# shield.net
KiCad netlist of a schematic drawn in EAGLE
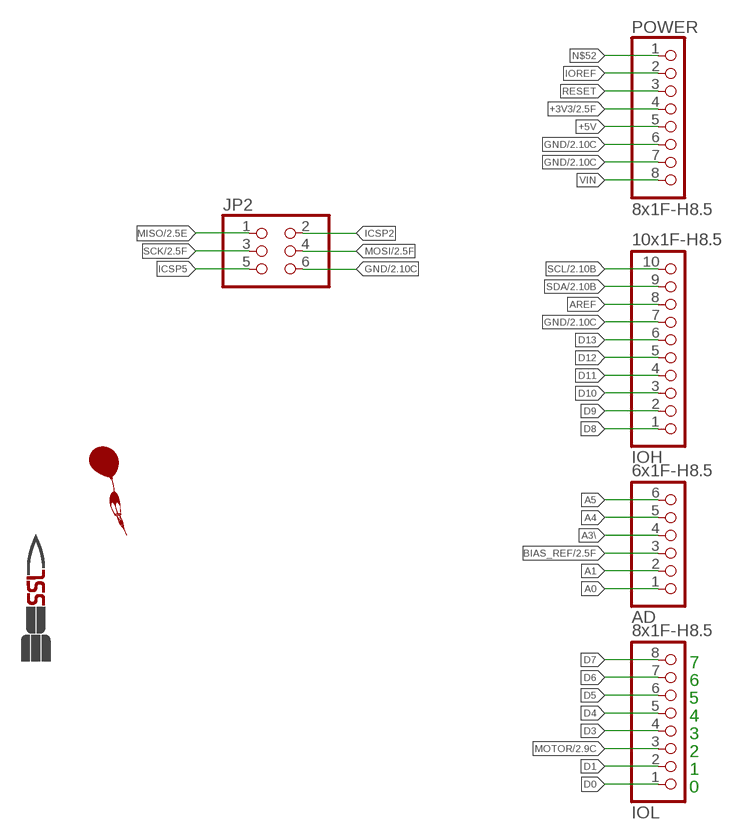
[diagram p0: schematic, sheet 1]
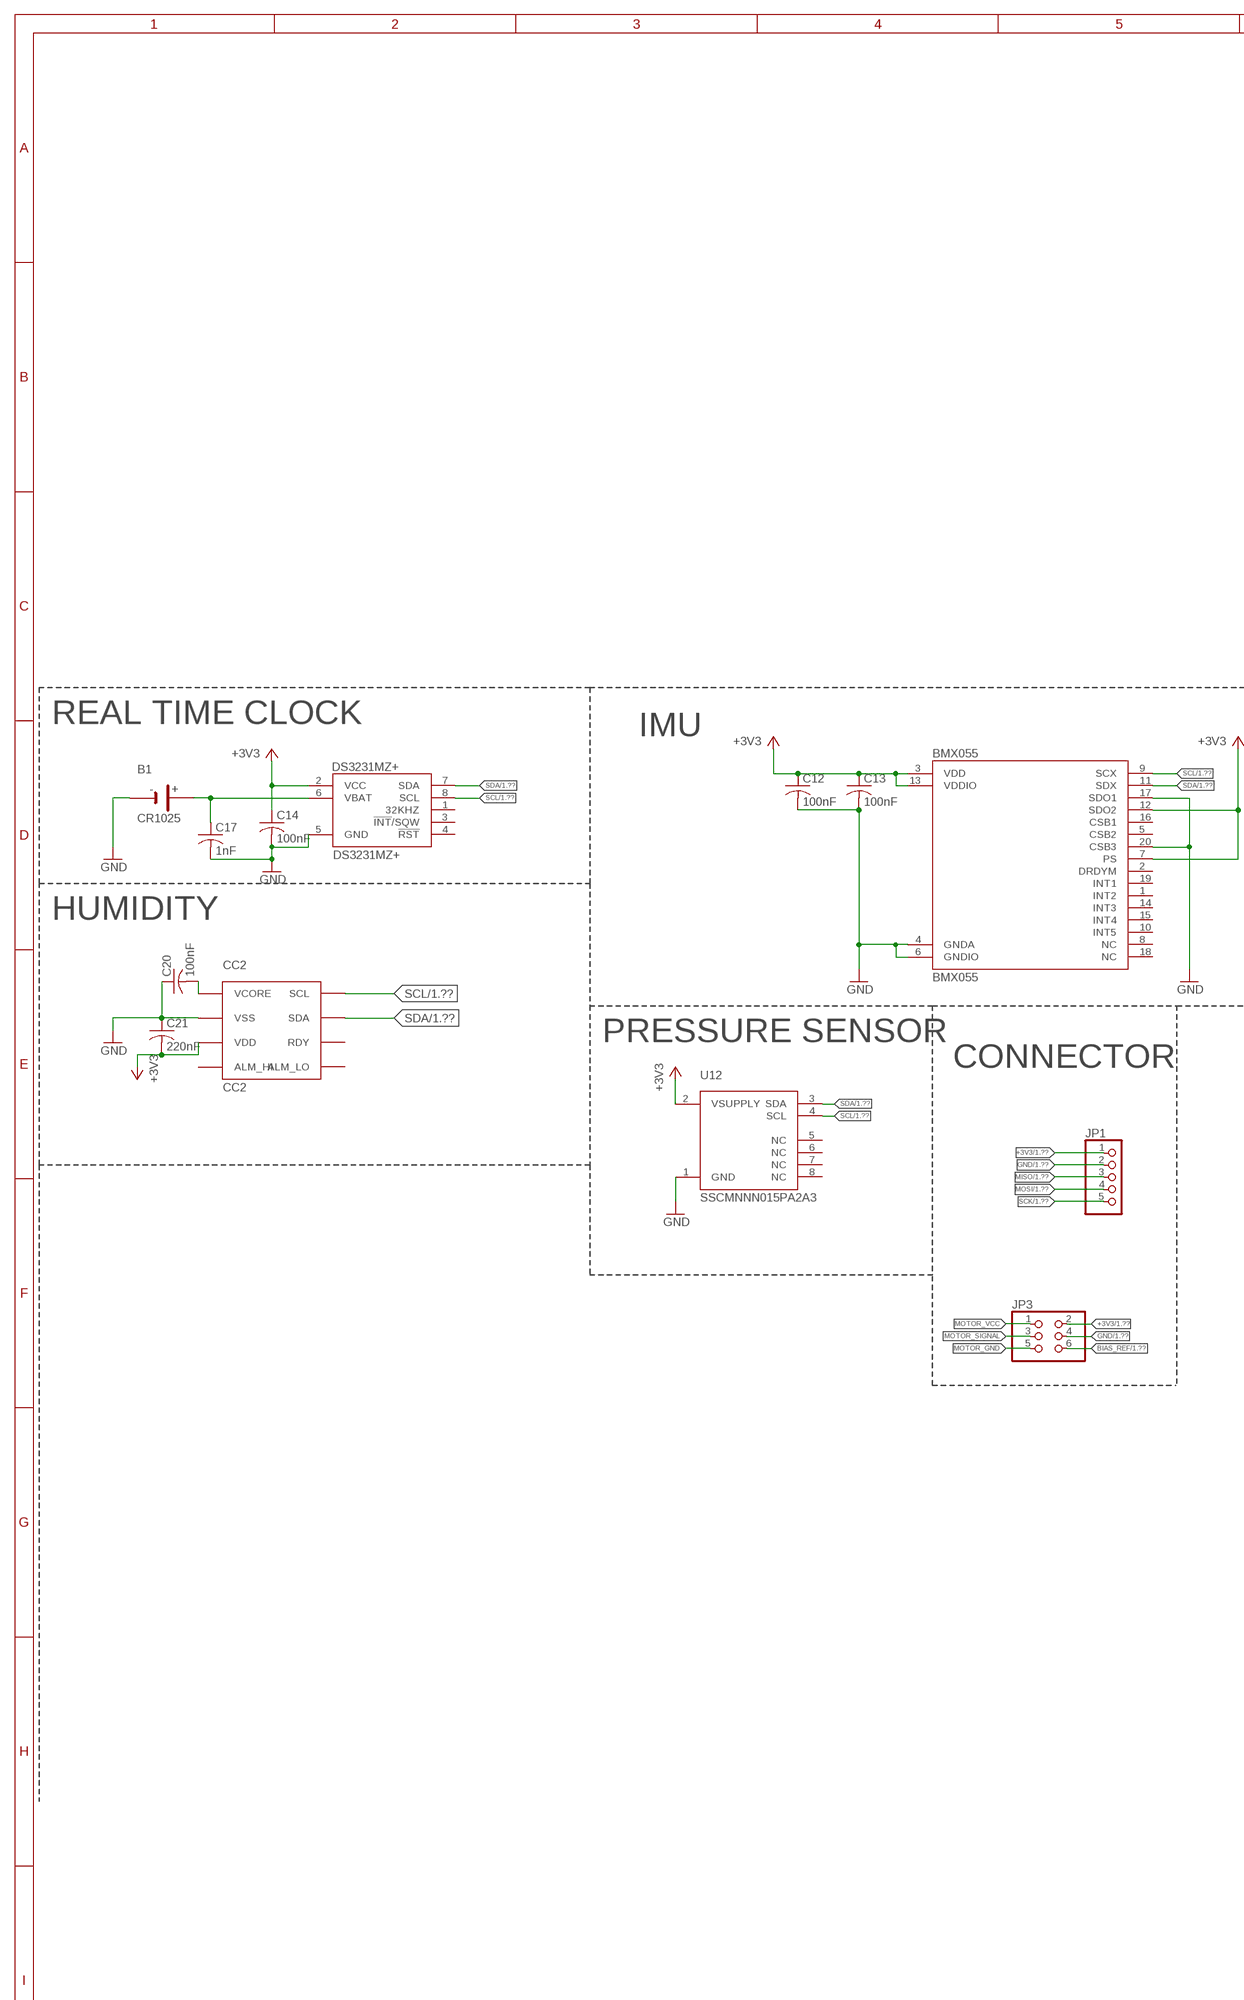
[diagram p1: schematic, sheet 2, part 1 of 2]
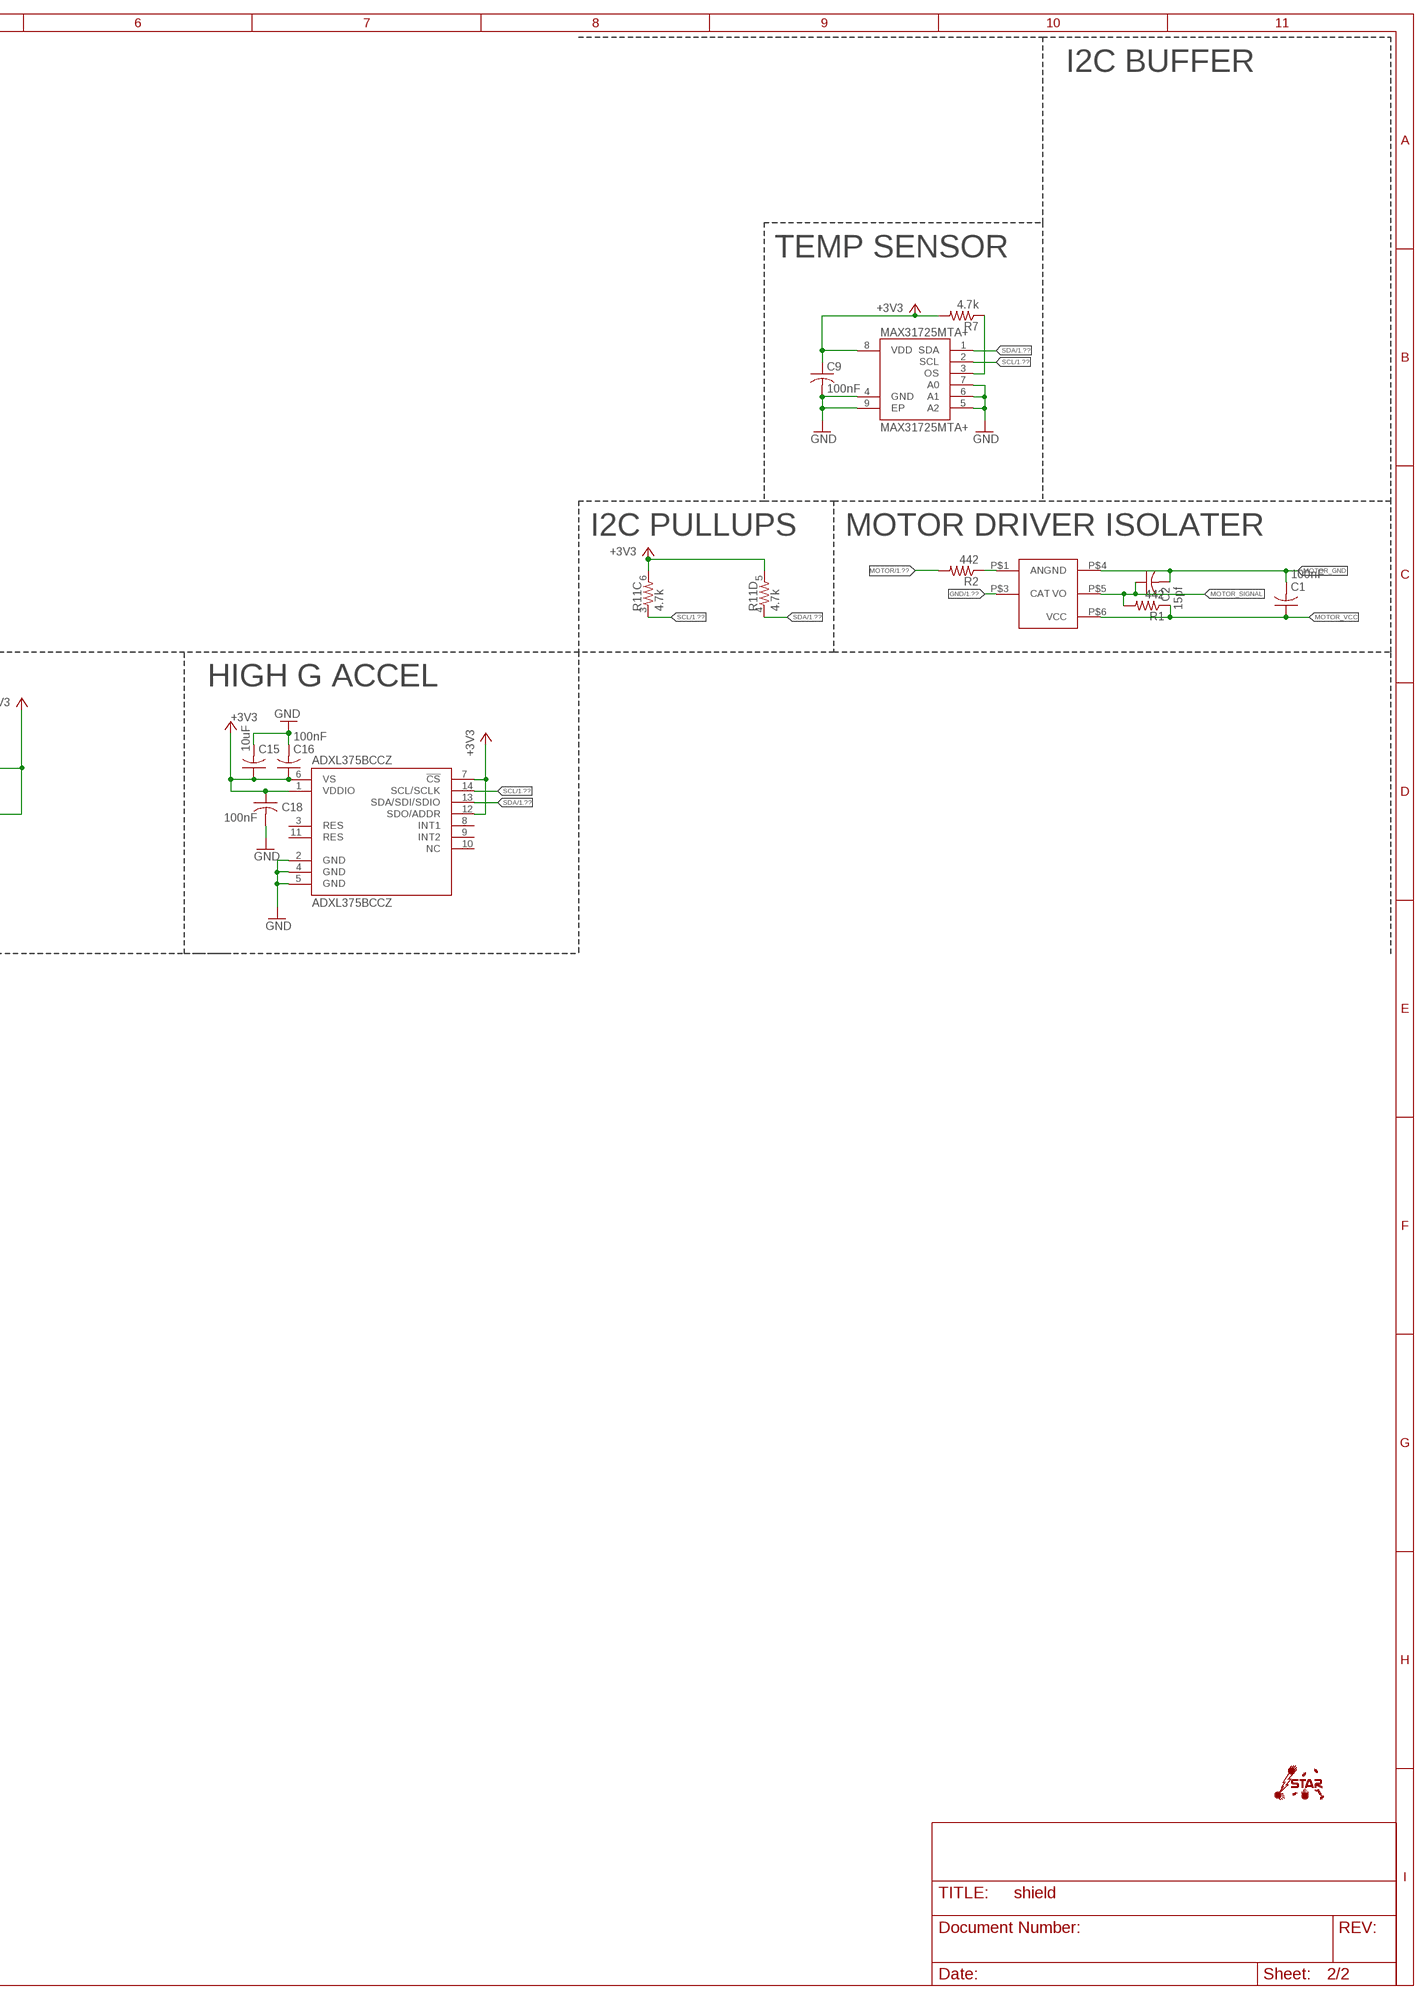
[diagram p2: schematic, sheet 2, part 2 of 2]

(export (version "E")
  (design (tool "Eeschema 10.0.6"))
  (components
    (comp (ref "AD")
      (value "6x1F-H8.5")
      (footprint "eagle-import:1X06")
      (libsource (lib "eagle-import") (part "PINHD-1X6"))
    )
    (comp (ref "IOH")
      (value "10x1F-H8.5")
      (footprint "eagle-import:1X10")
      (libsource (lib "eagle-import") (part "PINHD-1X10_ARD"))
    )
    (comp (ref "IOL")
      (value "8x1F-H8.5")
      (footprint "eagle-import:1X08")
      (libsource (lib "eagle-import") (part "PINHD-1X8"))
    )
    (comp (ref "JP2")
      (value "PINHD-2X3")
      (footprint "eagle-import:2X03")
      (libsource (lib "eagle-import") (part "pinhead_325_PINHD-2X3"))
    )
    (comp (ref "POWER")
      (value "8x1F-H8.5")
      (footprint "eagle-import:1X08")
      (libsource (lib "eagle-import") (part "PINHD-1X8"))
    )
    (comp (ref "U$1")
      (value "BALLOON")
      (footprint "eagle-import:BALLOON")
      (libsource (lib "eagle-import") (part "BALLOON"))
    )
    (comp (ref "U$2")
      (value "SSLORIG")
      (footprint "eagle-import:SSL")
      (libsource (lib "eagle-import") (part "SSLORIG"))
    )
    (comp (ref "ADXL375BCCZ")
      (value "ADXL375BCCZ")
      (footprint "eagle-import:LGA-14")
      (libsource (lib "eagle-import") (part "ADXL375BCCZ"))
    )
    (comp (ref "B1")
      (value "CR1025")
      (footprint "eagle-import:CR1025")
      (libsource (lib "eagle-import") (part "CR1025"))
    )
    (comp (ref "BMX055")
      (value "BMX055")
      (footprint "eagle-import:LGA-20")
      (libsource (lib "eagle-import") (part "BMX055"))
    )
    (comp (ref "C1")
      (value "100nF")
      (footprint "eagle-import:C0603")
      (libsource (lib "eagle-import") (part "C-USC0603"))
    )
    (comp (ref "C2")
      (value "15pf")
      (footprint "eagle-import:C0603")
      (libsource (lib "eagle-import") (part "C-USC0603"))
    )
    (comp (ref "C9")
      (value "100nF")
      (footprint "eagle-import:C0603")
      (libsource (lib "eagle-import") (part "C-USC0603"))
    )
    (comp (ref "C12")
      (value "100nF")
      (footprint "eagle-import:C0603")
      (libsource (lib "eagle-import") (part "C-USC0603"))
    )
    (comp (ref "C13")
      (value "100nF")
      (footprint "eagle-import:C0603")
      (libsource (lib "eagle-import") (part "C-USC0603"))
    )
    (comp (ref "C14")
      (value "100nF")
      (footprint "eagle-import:C0603")
      (libsource (lib "eagle-import") (part "C-USC0603"))
    )
    (comp (ref "C15")
      (value "10uF")
      (footprint "eagle-import:C0603")
      (libsource (lib "eagle-import") (part "C-USC0603"))
    )
    (comp (ref "C16")
      (value "100nF")
      (footprint "eagle-import:C0603")
      (libsource (lib "eagle-import") (part "C-USC0603"))
    )
    (comp (ref "C17")
      (value "1nF")
      (footprint "eagle-import:C0603")
      (libsource (lib "eagle-import") (part "C-USC0603"))
    )
    (comp (ref "C18")
      (value "100nF")
      (footprint "eagle-import:C0603")
      (libsource (lib "eagle-import") (part "C-USC0603"))
    )
    (comp (ref "C20")
      (value "100nF")
      (footprint "eagle-import:C0603")
      (libsource (lib "eagle-import") (part "C-USC0603"))
    )
    (comp (ref "C21")
      (value "220nF")
      (footprint "eagle-import:C0603")
      (libsource (lib "eagle-import") (part "C-USC0603"))
    )
    (comp (ref "CC2")
      (value "CC2")
      (footprint "eagle-import:CC2")
      (libsource (lib "eagle-import") (part "CC2"))
    )
    (comp (ref "DS3231MZ+")
      (value "DS3231MZ+")
      (footprint "eagle-import:SOIC-8")
      (libsource (lib "eagle-import") (part "DS3231MZ+"))
    )
    (comp (ref "IMAG2")
      (value "STAR")
      (footprint "eagle-import:STAR_.3IN")
      (libsource (lib "eagle-import") (part "STAR"))
    )
    (comp (ref "JP1")
      (value "PINHD-1X5")
      (footprint "eagle-import:1X05")
      (libsource (lib "eagle-import") (part "PINHD-1X5"))
    )
    (comp (ref "JP3")
      (value "PINHD-2X3")
      (footprint "eagle-import:2X03")
      (libsource (lib "eagle-import") (part "PINHD-2X3"))
    )
    (comp (ref "MAX31725MTA+")
      (value "MAX31725MTA+")
      (footprint "eagle-import:DFN-8")
      (libsource (lib "eagle-import") (part "MAX31725MTA+"))
    )
    (comp (ref "MOTORDRIVER")
      (value "FODM8061-D")
      (footprint "eagle-import:SO5")
      (libsource (lib "eagle-import") (part "FODM8061-D"))
    )
    (comp (ref "R1")
      (value "442")
      (footprint "eagle-import:R0805")
      (libsource (lib "eagle-import") (part "resistor_348_R-US_R0805"))
    )
    (comp (ref "R2")
      (value "442")
      (footprint "eagle-import:R0805")
      (libsource (lib "eagle-import") (part "resistor_348_R-US_R0805"))
    )
    (comp (ref "R7")
      (value "4.7k")
      (footprint "eagle-import:R0603")
      (libsource (lib "eagle-import") (part "R-US_R0603"))
    )
    (comp (ref "R11")
      (value "4.7k")
      (footprint "eagle-import:0603-ARV")
      (libsource (lib "eagle-import") (part "RESISTOR-ARRAY0603-ARV"))
    )
    (comp (ref "U12")
      (value "SSCMNNN015PA2A3")
      (footprint "eagle-import:HSC-SMT-8")
      (libsource (lib "eagle-import") (part "SSCMNNN015PA2A3"))
    )
  )
  (nets
    (net (code "1") (name "+3V3") (class "Default")
      (node (ref "ADXL375BCCZ") (pin "1") (pinfunction "VDDIO_1") (pintype "bidirectional"))
      (node (ref "ADXL375BCCZ") (pin "12") (pinfunction "SDO/ADDR_12") (pintype "bidirectional"))
      (node (ref "ADXL375BCCZ") (pin "6") (pinfunction "VS_6") (pintype "bidirectional"))
      (node (ref "ADXL375BCCZ") (pin "7") (pinfunction "~{CS}_7") (pintype "bidirectional"))
      (node (ref "BMX055") (pin "12") (pinfunction "SDO2_12") (pintype "bidirectional"))
      (node (ref "BMX055") (pin "13") (pinfunction "VDDIO_13") (pintype "power_in"))
      (node (ref "BMX055") (pin "3") (pinfunction "VDD_3") (pintype "power_in"))
      (node (ref "BMX055") (pin "7") (pinfunction "PS_7") (pintype "bidirectional"))
      (node (ref "C12") (pin "1") (pinfunction "1_1") (pintype "passive"))
      (node (ref "C13") (pin "1") (pinfunction "1_1") (pintype "passive"))
      (node (ref "C14") (pin "1") (pinfunction "1_1") (pintype "passive"))
      (node (ref "C15") (pin "1") (pinfunction "1_1") (pintype "passive"))
      (node (ref "C16") (pin "1") (pinfunction "1_1") (pintype "passive"))
      (node (ref "C18") (pin "1") (pinfunction "1_1") (pintype "passive"))
      (node (ref "C21") (pin "2") (pinfunction "2_2") (pintype "passive"))
      (node (ref "C9") (pin "1") (pinfunction "1_1") (pintype "passive"))
      (node (ref "CC2") (pin "P$7") (pinfunction "VDD_P$7") (pintype "power_in"))
      (node (ref "DS3231MZ+") (pin "2") (pinfunction "VCC_2") (pintype "power_in"))
      (node (ref "JP1") (pin "1") (pinfunction "1_1") (pintype "passive"))
      (node (ref "JP3") (pin "2") (pinfunction "2_2") (pintype "passive"))
      (node (ref "MAX31725MTA+") (pin "8") (pinfunction "VDD_8") (pintype "power_in"))
      (node (ref "POWER") (pin "4") (pinfunction "4_4") (pintype "passive"))
      (node (ref "R11") (pin "5") (pinfunction "2_5") (pintype "passive"))
      (node (ref "R11") (pin "6") (pinfunction "2_6") (pintype "passive"))
      (node (ref "R7") (pin "2") (pinfunction "2_2") (pintype "passive"))
      (node (ref "U12") (pin "2") (pinfunction "VSUPPLY_2") (pintype "power_in"))
    )
    (net (code "2") (name "+5V") (class "Default")
      (node (ref "POWER") (pin "5") (pinfunction "5_5") (pintype "passive"))
    )
    (net (code "3") (name "A0") (class "Default")
      (node (ref "AD") (pin "1") (pinfunction "1_1") (pintype "passive"))
    )
    (net (code "4") (name "A1") (class "Default")
      (node (ref "AD") (pin "2") (pinfunction "2_2") (pintype "passive"))
    )
    (net (code "5") (name "A3\\") (class "Default")
      (node (ref "AD") (pin "4") (pinfunction "4_4") (pintype "passive"))
    )
    (net (code "6") (name "A4") (class "Default")
      (node (ref "AD") (pin "5") (pinfunction "5_5") (pintype "passive"))
    )
    (net (code "7") (name "A5") (class "Default")
      (node (ref "AD") (pin "6") (pinfunction "6_6") (pintype "passive"))
    )
    (net (code "8") (name "AREF") (class "Default")
      (node (ref "IOH") (pin "8") (pinfunction "8_8") (pintype "passive"))
    )
    (net (code "9") (name "BIAS_REF") (class "Default")
      (node (ref "AD") (pin "3") (pinfunction "3_3") (pintype "passive"))
      (node (ref "JP3") (pin "6") (pinfunction "6_6") (pintype "passive"))
    )
    (net (code "10") (name "D0") (class "Default")
      (node (ref "IOL") (pin "1") (pinfunction "1_1") (pintype "passive"))
    )
    (net (code "11") (name "D1") (class "Default")
      (node (ref "IOL") (pin "2") (pinfunction "2_2") (pintype "passive"))
    )
    (net (code "12") (name "D3") (class "Default")
      (node (ref "IOL") (pin "4") (pinfunction "4_4") (pintype "passive"))
    )
    (net (code "13") (name "D4") (class "Default")
      (node (ref "IOL") (pin "5") (pinfunction "5_5") (pintype "passive"))
    )
    (net (code "14") (name "D5") (class "Default")
      (node (ref "IOL") (pin "6") (pinfunction "6_6") (pintype "passive"))
    )
    (net (code "15") (name "D6") (class "Default")
      (node (ref "IOL") (pin "7") (pinfunction "7_7") (pintype "passive"))
    )
    (net (code "16") (name "D7") (class "Default")
      (node (ref "IOL") (pin "8") (pinfunction "8_8") (pintype "passive"))
    )
    (net (code "17") (name "D8") (class "Default")
      (node (ref "IOH") (pin "1") (pinfunction "1_1") (pintype "passive"))
    )
    (net (code "18") (name "D9") (class "Default")
      (node (ref "IOH") (pin "2") (pinfunction "2_2") (pintype "passive"))
    )
    (net (code "19") (name "D10") (class "Default")
      (node (ref "IOH") (pin "3") (pinfunction "3_3") (pintype "passive"))
    )
    (net (code "20") (name "D11") (class "Default")
      (node (ref "IOH") (pin "4") (pinfunction "4_4") (pintype "passive"))
    )
    (net (code "21") (name "D12") (class "Default")
      (node (ref "IOH") (pin "5") (pinfunction "5_5") (pintype "passive"))
    )
    (net (code "22") (name "D13") (class "Default")
      (node (ref "IOH") (pin "6") (pinfunction "6_6") (pintype "passive"))
    )
    (net (code "23") (name "GND") (class "Default")
      (node (ref "ADXL375BCCZ") (pin "2") (pinfunction "GND_2") (pintype "bidirectional"))
      (node (ref "ADXL375BCCZ") (pin "4") (pinfunction "GND_4") (pintype "bidirectional"))
      (node (ref "ADXL375BCCZ") (pin "5") (pinfunction "GND_5") (pintype "bidirectional"))
      (node (ref "B1") (pin "3") (pinfunction "-_3") (pintype "power_in"))
      (node (ref "BMX055") (pin "17") (pinfunction "SDO1_17") (pintype "bidirectional"))
      (node (ref "BMX055") (pin "20") (pinfunction "CSB3_20") (pintype "bidirectional"))
      (node (ref "BMX055") (pin "4") (pinfunction "GNDA_4") (pintype "power_in"))
      (node (ref "BMX055") (pin "6") (pinfunction "GNDIO_6") (pintype "power_in"))
      (node (ref "C12") (pin "2") (pinfunction "2_2") (pintype "passive"))
      (node (ref "C13") (pin "2") (pinfunction "2_2") (pintype "passive"))
      (node (ref "C14") (pin "2") (pinfunction "2_2") (pintype "passive"))
      (node (ref "C15") (pin "2") (pinfunction "2_2") (pintype "passive"))
      (node (ref "C16") (pin "2") (pinfunction "2_2") (pintype "passive"))
      (node (ref "C17") (pin "2") (pinfunction "2_2") (pintype "passive"))
      (node (ref "C18") (pin "2") (pinfunction "2_2") (pintype "passive"))
      (node (ref "C20") (pin "1") (pinfunction "1_1") (pintype "passive"))
      (node (ref "C21") (pin "1") (pinfunction "1_1") (pintype "passive"))
      (node (ref "C9") (pin "2") (pinfunction "2_2") (pintype "passive"))
      (node (ref "CC2") (pin "P$6") (pinfunction "VSS_P$6") (pintype "power_in"))
      (node (ref "DS3231MZ+") (pin "5") (pinfunction "GND_5") (pintype "power_in"))
      (node (ref "IOH") (pin "7") (pinfunction "7_7") (pintype "passive"))
      (node (ref "JP1") (pin "2") (pinfunction "2_2") (pintype "passive"))
      (node (ref "JP2") (pin "6") (pinfunction "6_6") (pintype "passive"))
      (node (ref "JP3") (pin "4") (pinfunction "4_4") (pintype "passive"))
      (node (ref "MAX31725MTA+") (pin "4") (pinfunction "GND_4") (pintype "power_in"))
      (node (ref "MAX31725MTA+") (pin "5") (pinfunction "A2_5") (pintype "bidirectional"))
      (node (ref "MAX31725MTA+") (pin "6") (pinfunction "A1_6") (pintype "bidirectional"))
      (node (ref "MAX31725MTA+") (pin "7") (pinfunction "A0_7") (pintype "bidirectional"))
      (node (ref "MAX31725MTA+") (pin "9") (pinfunction "EP_9") (pintype "power_in"))
      (node (ref "MOTORDRIVER") (pin "P$3") (pinfunction "CAT_P$3") (pintype "bidirectional"))
      (node (ref "POWER") (pin "6") (pinfunction "6_6") (pintype "passive"))
      (node (ref "POWER") (pin "7") (pinfunction "7_7") (pintype "passive"))
      (node (ref "U12") (pin "1") (pinfunction "GND_1") (pintype "power_in"))
    )
    (net (code "24") (name "ICSP2") (class "Default")
      (node (ref "JP2") (pin "2") (pinfunction "2_2") (pintype "passive"))
    )
    (net (code "25") (name "ICSP5") (class "Default")
      (node (ref "JP2") (pin "5") (pinfunction "5_5") (pintype "passive"))
    )
    (net (code "26") (name "IOREF") (class "Default")
      (node (ref "POWER") (pin "2") (pinfunction "2_2") (pintype "passive"))
    )
    (net (code "27") (name "MISO") (class "Default")
      (node (ref "JP1") (pin "3") (pinfunction "3_3") (pintype "passive"))
      (node (ref "JP2") (pin "1") (pinfunction "1_1") (pintype "passive"))
    )
    (net (code "28") (name "MOSI") (class "Default")
      (node (ref "JP1") (pin "4") (pinfunction "4_4") (pintype "passive"))
      (node (ref "JP2") (pin "4") (pinfunction "4_4") (pintype "passive"))
    )
    (net (code "29") (name "MOTOR") (class "Default")
      (node (ref "IOL") (pin "3") (pinfunction "3_3") (pintype "passive"))
      (node (ref "R2") (pin "2") (pinfunction "2_2") (pintype "passive"))
    )
    (net (code "30") (name "MOTOR_GND") (class "Default")
      (node (ref "C1") (pin "2") (pinfunction "2_2") (pintype "passive"))
      (node (ref "C2") (pin "2") (pinfunction "2_2") (pintype "passive"))
      (node (ref "JP3") (pin "5") (pinfunction "5_5") (pintype "passive"))
      (node (ref "MOTORDRIVER") (pin "P$4") (pinfunction "GND_P$4") (pintype "bidirectional"))
    )
    (net (code "31") (name "MOTOR_SIGNAL") (class "Default")
      (node (ref "C2") (pin "1") (pinfunction "1_1") (pintype "passive"))
      (node (ref "JP3") (pin "3") (pinfunction "3_3") (pintype "passive"))
      (node (ref "MOTORDRIVER") (pin "P$5") (pinfunction "VO_P$5") (pintype "bidirectional"))
      (node (ref "R1") (pin "2") (pinfunction "2_2") (pintype "passive"))
    )
    (net (code "32") (name "MOTOR_VCC") (class "Default")
      (node (ref "C1") (pin "1") (pinfunction "1_1") (pintype "passive"))
      (node (ref "JP3") (pin "1") (pinfunction "1_1") (pintype "passive"))
      (node (ref "MOTORDRIVER") (pin "P$6") (pinfunction "VCC_P$6") (pintype "bidirectional"))
      (node (ref "R1") (pin "1") (pinfunction "1_1") (pintype "passive"))
    )
    (net (code "33") (name "N$52") (class "Default")
      (node (ref "POWER") (pin "1") (pinfunction "1_1") (pintype "passive"))
    )
    (net (code "34") (name "Net-(CC2-VCORE)") (class "Default")
      (node (ref "C20") (pin "2") (pinfunction "2_2") (pintype "passive"))
      (node (ref "CC2") (pin "P$5") (pinfunction "VCORE_P$5") (pintype "power_in"))
    )
    (net (code "35") (name "Net-(DS3231MZ+-VBAT)") (class "Default")
      (node (ref "B1") (pin "1") (pinfunction "+_1") (pintype "power_in"))
      (node (ref "B1") (pin "2") (pinfunction "+_2") (pintype "power_in"))
      (node (ref "C17") (pin "1") (pinfunction "1_1") (pintype "passive"))
      (node (ref "DS3231MZ+") (pin "6") (pinfunction "VBAT_6") (pintype "power_in"))
    )
    (net (code "36") (name "Net-(MAX31725MTA+-OS)") (class "Default")
      (node (ref "MAX31725MTA+") (pin "3") (pinfunction "OS_3") (pintype "bidirectional"))
      (node (ref "R7") (pin "1") (pinfunction "1_1") (pintype "passive"))
    )
    (net (code "37") (name "Net-(MOTORDRIVER-AN)") (class "Default")
      (node (ref "MOTORDRIVER") (pin "P$1") (pinfunction "AN_P$1") (pintype "bidirectional"))
      (node (ref "R2") (pin "1") (pinfunction "1_1") (pintype "passive"))
    )
    (net (code "38") (name "RESET") (class "Default")
      (node (ref "POWER") (pin "3") (pinfunction "3_3") (pintype "passive"))
    )
    (net (code "39") (name "SCK") (class "Default")
      (node (ref "JP1") (pin "5") (pinfunction "5_5") (pintype "passive"))
      (node (ref "JP2") (pin "3") (pinfunction "3_3") (pintype "passive"))
    )
    (net (code "40") (name "SCL") (class "Default")
      (node (ref "ADXL375BCCZ") (pin "14") (pinfunction "SCL/SCLK_14") (pintype "bidirectional"))
      (node (ref "BMX055") (pin "9") (pinfunction "SCX_9") (pintype "bidirectional"))
      (node (ref "CC2") (pin "P$4") (pinfunction "SCL_P$4") (pintype "bidirectional"))
      (node (ref "DS3231MZ+") (pin "8") (pinfunction "SCL_8") (pintype "bidirectional"))
      (node (ref "IOH") (pin "10") (pinfunction "10_10") (pintype "passive"))
      (node (ref "MAX31725MTA+") (pin "2") (pinfunction "SCL_2") (pintype "bidirectional"))
      (node (ref "R11") (pin "3") (pinfunction "1_3") (pintype "passive"))
      (node (ref "U12") (pin "4") (pinfunction "SCL_4") (pintype "bidirectional"))
    )
    (net (code "41") (name "SDA") (class "Default")
      (node (ref "ADXL375BCCZ") (pin "13") (pinfunction "SDA/SDI/SDIO_13") (pintype "bidirectional"))
      (node (ref "BMX055") (pin "11") (pinfunction "SDX_11") (pintype "bidirectional"))
      (node (ref "CC2") (pin "P$3") (pinfunction "SDA_P$3") (pintype "bidirectional"))
      (node (ref "DS3231MZ+") (pin "7") (pinfunction "SDA_7") (pintype "bidirectional"))
      (node (ref "IOH") (pin "9") (pinfunction "9_9") (pintype "passive"))
      (node (ref "MAX31725MTA+") (pin "1") (pinfunction "SDA_1") (pintype "bidirectional"))
      (node (ref "R11") (pin "4") (pinfunction "1_4") (pintype "passive"))
      (node (ref "U12") (pin "3") (pinfunction "SDA_3") (pintype "bidirectional"))
    )
    (net (code "42") (name "VIN") (class "Default")
      (node (ref "POWER") (pin "8") (pinfunction "8_8") (pintype "passive"))
    )
    (net (code "43") (name "unconnected-(ADXL375BCCZ-INT1-Pad8)") (class "Default")
      (node (ref "ADXL375BCCZ") (pin "8") (pinfunction "INT1_8") (pintype "bidirectional"))
    )
    (net (code "44") (name "unconnected-(ADXL375BCCZ-INT2-Pad9)") (class "Default")
      (node (ref "ADXL375BCCZ") (pin "9") (pinfunction "INT2_9") (pintype "bidirectional"))
    )
    (net (code "45") (name "unconnected-(ADXL375BCCZ-NC-Pad10)") (class "Default")
      (node (ref "ADXL375BCCZ") (pin "10") (pinfunction "NC_10") (pintype "no_connect"))
    )
    (net (code "46") (name "unconnected-(ADXL375BCCZ-RES-Pad3)") (class "Default")
      (node (ref "ADXL375BCCZ") (pin "3") (pinfunction "RES_3") (pintype "bidirectional"))
    )
    (net (code "47") (name "unconnected-(ADXL375BCCZ-RES-Pad11)") (class "Default")
      (node (ref "ADXL375BCCZ") (pin "11") (pinfunction "RES_11") (pintype "bidirectional"))
    )
    (net (code "48") (name "unconnected-(BMX055-CSB1-Pad16)") (class "Default")
      (node (ref "BMX055") (pin "16") (pinfunction "CSB1_16") (pintype "bidirectional"))
    )
    (net (code "49") (name "unconnected-(BMX055-CSB2-Pad5)") (class "Default")
      (node (ref "BMX055") (pin "5") (pinfunction "CSB2_5") (pintype "bidirectional"))
    )
    (net (code "50") (name "unconnected-(BMX055-DRDYM-Pad2)") (class "Default")
      (node (ref "BMX055") (pin "2") (pinfunction "DRDYM_2") (pintype "bidirectional"))
    )
    (net (code "51") (name "unconnected-(BMX055-INT1-Pad19)") (class "Default")
      (node (ref "BMX055") (pin "19") (pinfunction "INT1_19") (pintype "bidirectional"))
    )
    (net (code "52") (name "unconnected-(BMX055-INT2-Pad1)") (class "Default")
      (node (ref "BMX055") (pin "1") (pinfunction "INT2_1") (pintype "bidirectional"))
    )
    (net (code "53") (name "unconnected-(BMX055-INT3-Pad14)") (class "Default")
      (node (ref "BMX055") (pin "14") (pinfunction "INT3_14") (pintype "bidirectional"))
    )
    (net (code "54") (name "unconnected-(BMX055-INT4-Pad15)") (class "Default")
      (node (ref "BMX055") (pin "15") (pinfunction "INT4_15") (pintype "bidirectional"))
    )
    (net (code "55") (name "unconnected-(BMX055-INT5-Pad10)") (class "Default")
      (node (ref "BMX055") (pin "10") (pinfunction "INT5_10") (pintype "bidirectional"))
    )
    (net (code "56") (name "unconnected-(BMX055-NC-Pad8)") (class "Default")
      (node (ref "BMX055") (pin "8") (pinfunction "NC_8") (pintype "no_connect"))
    )
    (net (code "57") (name "unconnected-(BMX055-NC-Pad18)") (class "Default")
      (node (ref "BMX055") (pin "18") (pinfunction "NC_18") (pintype "no_connect"))
    )
    (net (code "58") (name "unconnected-(CC2-ALM_HI-PadP$8)") (class "Default")
      (node (ref "CC2") (pin "P$8") (pinfunction "ALM_HI_P$8") (pintype "bidirectional"))
    )
    (net (code "59") (name "unconnected-(CC2-ALM_LO-PadP$1)") (class "Default")
      (node (ref "CC2") (pin "P$1") (pinfunction "ALM_LO_P$1") (pintype "bidirectional"))
    )
    (net (code "60") (name "unconnected-(CC2-RDY-PadP$2)") (class "Default")
      (node (ref "CC2") (pin "P$2") (pinfunction "RDY_P$2") (pintype "bidirectional"))
    )
    (net (code "61") (name "unconnected-(DS3231MZ+-32KHZ-Pad1)") (class "Default")
      (node (ref "DS3231MZ+") (pin "1") (pinfunction "32KHZ_1") (pintype "bidirectional"))
    )
    (net (code "62") (name "unconnected-(DS3231MZ+-~{INT}{slash}SQW-Pad3)") (class "Default")
      (node (ref "DS3231MZ+") (pin "3") (pinfunction "~{INT}/SQW_3") (pintype "bidirectional"))
    )
    (net (code "63") (name "unconnected-(DS3231MZ+-~{RST}-Pad4)") (class "Default")
      (node (ref "DS3231MZ+") (pin "4") (pinfunction "~{RST}_4") (pintype "bidirectional"))
    )
    (net (code "64") (name "unconnected-(U12-NC-Pad5)") (class "Default")
      (node (ref "U12") (pin "5") (pinfunction "NC_5") (pintype "no_connect"))
    )
    (net (code "65") (name "unconnected-(U12-NC-Pad6)") (class "Default")
      (node (ref "U12") (pin "6") (pinfunction "NC_6") (pintype "no_connect"))
    )
    (net (code "66") (name "unconnected-(U12-NC-Pad7)") (class "Default")
      (node (ref "U12") (pin "7") (pinfunction "NC_7") (pintype "no_connect"))
    )
    (net (code "67") (name "unconnected-(U12-NC-Pad8)") (class "Default")
      (node (ref "U12") (pin "8") (pinfunction "NC_8") (pintype "no_connect"))
    )
  )
)
